# on-connector_PCB.net
KiCad netlist of a schematic drawn in EAGLE
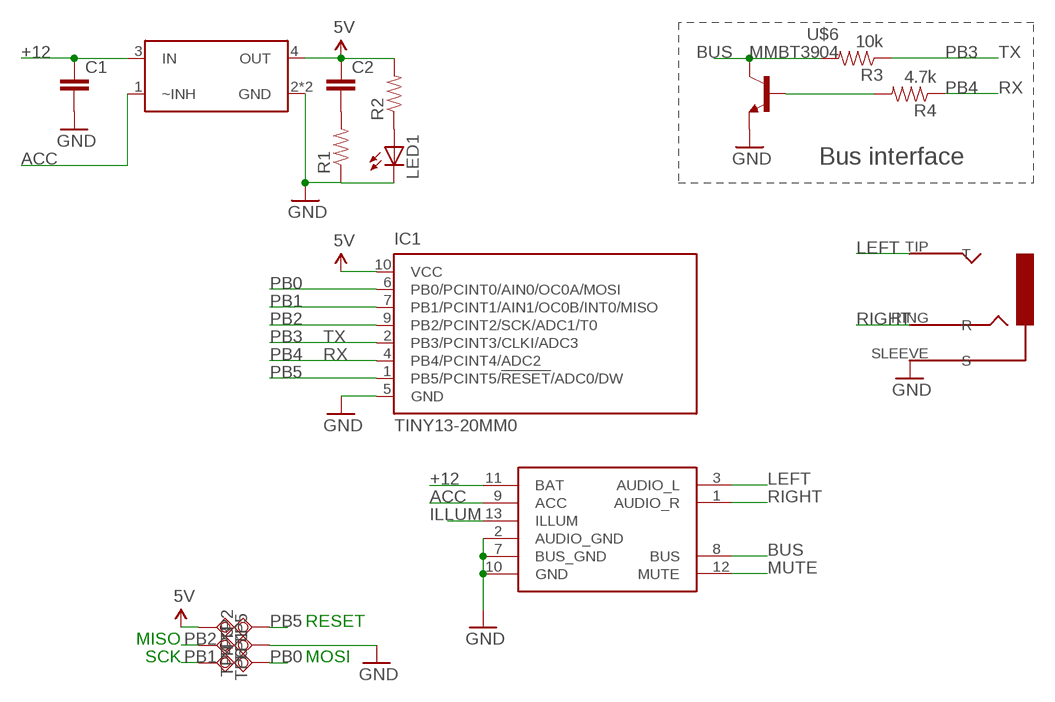
[diagram p0: schematic, sheet 1]

(export (version "E")
  (design (tool "Eeschema 10.0.6"))
  (components
    (comp (ref "C1")
      (value "CAP0603-CAP")
      (footprint "eagle-import:0603-CAP")
      (libsource (lib "eagle-import") (part "CAP0603-CAP"))
    )
    (comp (ref "C2")
      (value "CAP0603-CAP")
      (footprint "eagle-import:0603-CAP")
      (libsource (lib "eagle-import") (part "CAP0603-CAP"))
    )
    (comp (ref "IC1")
      (value "TINY13-20MM0")
      (footprint "eagle-import:10M1")
      (fields (field (name "MPN") "ATTINY13A-MMU"))
      (libsource (lib "eagle-import") (part "TINY13MM0-20"))
    )
    (comp (ref "LED1")
      (value "LED0603")
      (footprint "eagle-import:LED-0603")
      (libsource (lib "eagle-import") (part "LED0603"))
    )
    (comp (ref "R1")
      (value "RESISTOR0603-RES")
      (footprint "eagle-import:0603-RES")
      (libsource (lib "eagle-import") (part "RESISTOR0603-RES"))
    )
    (comp (ref "R2")
      (value "RESISTOR0603-RES")
      (footprint "eagle-import:0603-RES")
      (libsource (lib "eagle-import") (part "RESISTOR0603-RES"))
    )
    (comp (ref "R3")
      (value "10k")
      (footprint "eagle-import:0805")
      (libsource (lib "eagle-import") (part "RESISTOR0805-RES"))
    )
    (comp (ref "R4")
      (value "4.7k")
      (footprint "eagle-import:0805")
      (libsource (lib "eagle-import") (part "RESISTOR0805-RES"))
    )
    (comp (ref "TP1")
      (value "TPSQTP07R")
      (footprint "eagle-import:TP07R")
      (libsource (lib "eagle-import") (part "TPSQTP07R"))
    )
    (comp (ref "TP2")
      (value "TPSQTP07R")
      (footprint "eagle-import:TP07R")
      (libsource (lib "eagle-import") (part "TPSQTP07R"))
    )
    (comp (ref "TP3")
      (value "TPSQTP07R")
      (footprint "eagle-import:TP07R")
      (libsource (lib "eagle-import") (part "TPSQTP07R"))
    )
    (comp (ref "TP4")
      (value "TPSQTP07R")
      (footprint "eagle-import:TP07R")
      (libsource (lib "eagle-import") (part "TPSQTP07R"))
    )
    (comp (ref "TP5")
      (value "TPSQTP07SQ")
      (footprint "eagle-import:TP07SQ")
      (libsource (lib "eagle-import") (part "TPSQTP07SQ"))
    )
    (comp (ref "TP6")
      (value "TPSQTP07R")
      (footprint "eagle-import:TP07R")
      (libsource (lib "eagle-import") (part "TPSQTP07R"))
    )
    (comp (ref "U$1")
      (value "PANASONIC_CN702_BACKBOARD")
      (footprint "eagle-import:040_MLCII_BACK_CN702")
      (libsource (lib "eagle-import") (part "PANASONIC_CN702_BACKBOARD"))
    )
    (comp (ref "U$2")
      (value "STEREO_JACK_SJ_352X")
      (footprint "eagle-import:AUDIO-JACK-3.5MM-SMD")
      (libsource (lib "eagle-import") (part "STEREO_JACK_SJ_352X"))
    )
    (comp (ref "U$6")
      (value "MMBT3904")
      (footprint "eagle-import:SOT23-3")
      (libsource (lib "eagle-import") (part "MMBT3904"))
    )
    (comp (ref "U$7")
      (value "IFX20001")
      (footprint "eagle-import:PG-SCT595-5")
      (libsource (lib "eagle-import") (part "IFX20001"))
    )
  )
  (nets
    (net (code "1") (name "/+12") (class "Default")
      (node (ref "C1") (pin "1") (pinfunction "1_1") (pintype "passive"))
      (node (ref "U$1") (pin "11") (pinfunction "BAT_11") (pintype "bidirectional"))
      (node (ref "U$7") (pin "3") (pinfunction "IN_3") (pintype "bidirectional"))
    )
    (net (code "2") (name "/ACC") (class "Default")
      (node (ref "U$1") (pin "9") (pinfunction "ACC_9") (pintype "bidirectional"))
      (node (ref "U$7") (pin "1") (pinfunction "~{INH}_1") (pintype "bidirectional"))
    )
    (net (code "3") (name "/BUS") (class "Default")
      (node (ref "R3") (pin "2") (pinfunction "2_2") (pintype "passive"))
      (node (ref "U$1") (pin "8") (pinfunction "BUS_8") (pintype "bidirectional"))
      (node (ref "U$6") (pin "3") (pinfunction "C_3") (pintype "passive"))
    )
    (net (code "4") (name "/ILLUM") (class "Default")
      (node (ref "U$1") (pin "13") (pinfunction "ILLUM_13") (pintype "bidirectional"))
    )
    (net (code "5") (name "/LEFT") (class "Default")
      (node (ref "U$1") (pin "3") (pinfunction "AUDIO_L_3") (pintype "bidirectional"))
      (node (ref "U$2") (pin "TIP") (pinfunction "T_TIP") (pintype "passive"))
    )
    (net (code "6") (name "/MUTE") (class "Default")
      (node (ref "U$1") (pin "12") (pinfunction "MUTE_12") (pintype "bidirectional"))
    )
    (net (code "7") (name "/PB0") (class "Default")
      (node (ref "IC1") (pin "6") (pinfunction "PB0/PCINT0/AIN0/OC0A/MOSI_6") (pintype "bidirectional"))
      (node (ref "TP4") (pin "TP") (pinfunction "TP_TP") (pintype "input"))
    )
    (net (code "8") (name "/PB1") (class "Default")
      (node (ref "IC1") (pin "7") (pinfunction "PB1/PCINT1/AIN1/OC0B/INT0/MISO_7") (pintype "bidirectional"))
      (node (ref "TP6") (pin "TP") (pinfunction "TP_TP") (pintype "input"))
    )
    (net (code "9") (name "/PB2") (class "Default")
      (node (ref "IC1") (pin "9") (pinfunction "PB2/PCINT2/SCK/ADC1/T0_9") (pintype "bidirectional"))
      (node (ref "TP1") (pin "TP") (pinfunction "TP_TP") (pintype "input"))
    )
    (net (code "10") (name "/PB3") (class "Default")
      (node (ref "IC1") (pin "2") (pinfunction "PB3/PCINT3/CLKI/ADC3_2") (pintype "bidirectional"))
      (node (ref "R3") (pin "1") (pinfunction "1_1") (pintype "passive"))
    )
    (net (code "11") (name "/PB4") (class "Default")
      (node (ref "IC1") (pin "4") (pinfunction "PB4/PCINT4/ADC2_4") (pintype "bidirectional"))
      (node (ref "R4") (pin "1") (pinfunction "1_1") (pintype "passive"))
    )
    (net (code "12") (name "/PB5") (class "Default")
      (node (ref "IC1") (pin "1") (pinfunction "PB5/PCINT5/~{RESET}/ADC0/DW_1") (pintype "bidirectional"))
      (node (ref "TP2") (pin "TP") (pinfunction "TP_TP") (pintype "input"))
    )
    (net (code "13") (name "/RIGHT") (class "Default")
      (node (ref "U$1") (pin "1") (pinfunction "AUDIO_R_1") (pintype "bidirectional"))
      (node (ref "U$2") (pin "RING") (pinfunction "R_RING") (pintype "passive"))
    )
    (net (code "14") (name "5V") (class "Default")
      (node (ref "C2") (pin "1") (pinfunction "1_1") (pintype "passive"))
      (node (ref "IC1") (pin "10") (pinfunction "VCC_10") (pintype "power_in"))
      (node (ref "R2") (pin "2") (pinfunction "2_2") (pintype "passive"))
      (node (ref "TP5") (pin "TP") (pinfunction "TP_TP") (pintype "input"))
      (node (ref "U$7") (pin "4") (pinfunction "OUT_4") (pintype "bidirectional"))
    )
    (net (code "15") (name "GND") (class "Default")
      (node (ref "C1") (pin "2") (pinfunction "2_2") (pintype "passive"))
      (node (ref "IC1") (pin "5") (pinfunction "GND_5") (pintype "power_in"))
      (node (ref "LED1") (pin "C") (pinfunction "C_C") (pintype "passive"))
      (node (ref "R1") (pin "1") (pinfunction "1_1") (pintype "passive"))
      (node (ref "TP3") (pin "TP") (pinfunction "TP_TP") (pintype "input"))
      (node (ref "U$1") (pin "10") (pinfunction "GND_10") (pintype "bidirectional"))
      (node (ref "U$1") (pin "2") (pinfunction "AUDIO_GND_2") (pintype "bidirectional"))
      (node (ref "U$1") (pin "7") (pinfunction "BUS_GND_7") (pintype "bidirectional"))
      (node (ref "U$2") (pin "SLEEVE") (pinfunction "S_SLEEVE") (pintype "passive"))
      (node (ref "U$6") (pin "2") (pinfunction "E_2") (pintype "passive"))
      (node (ref "U$7") (pin "2") (pinfunction "GND_2") (pintype "bidirectional"))
      (node (ref "U$7") (pin "5") (pinfunction "GND_5") (pintype "bidirectional"))
    )
    (net (code "16") (name "Net-(C2-Pad2)") (class "Default")
      (node (ref "C2") (pin "2") (pinfunction "2_2") (pintype "passive"))
      (node (ref "R1") (pin "2") (pinfunction "2_2") (pintype "passive"))
    )
    (net (code "17") (name "Net-(LED1-PadA)") (class "Default")
      (node (ref "LED1") (pin "A") (pinfunction "A_A") (pintype "passive"))
      (node (ref "R2") (pin "1") (pinfunction "1_1") (pintype "passive"))
    )
    (net (code "18") (name "Net-(U$6-B)") (class "Default")
      (node (ref "R4") (pin "2") (pinfunction "2_2") (pintype "passive"))
      (node (ref "U$6") (pin "1") (pinfunction "B_1") (pintype "passive"))
    )
  )
)
